# Battery_Tree_V2.net
KiCad netlist of a schematic drawn in EasyEDA Pro
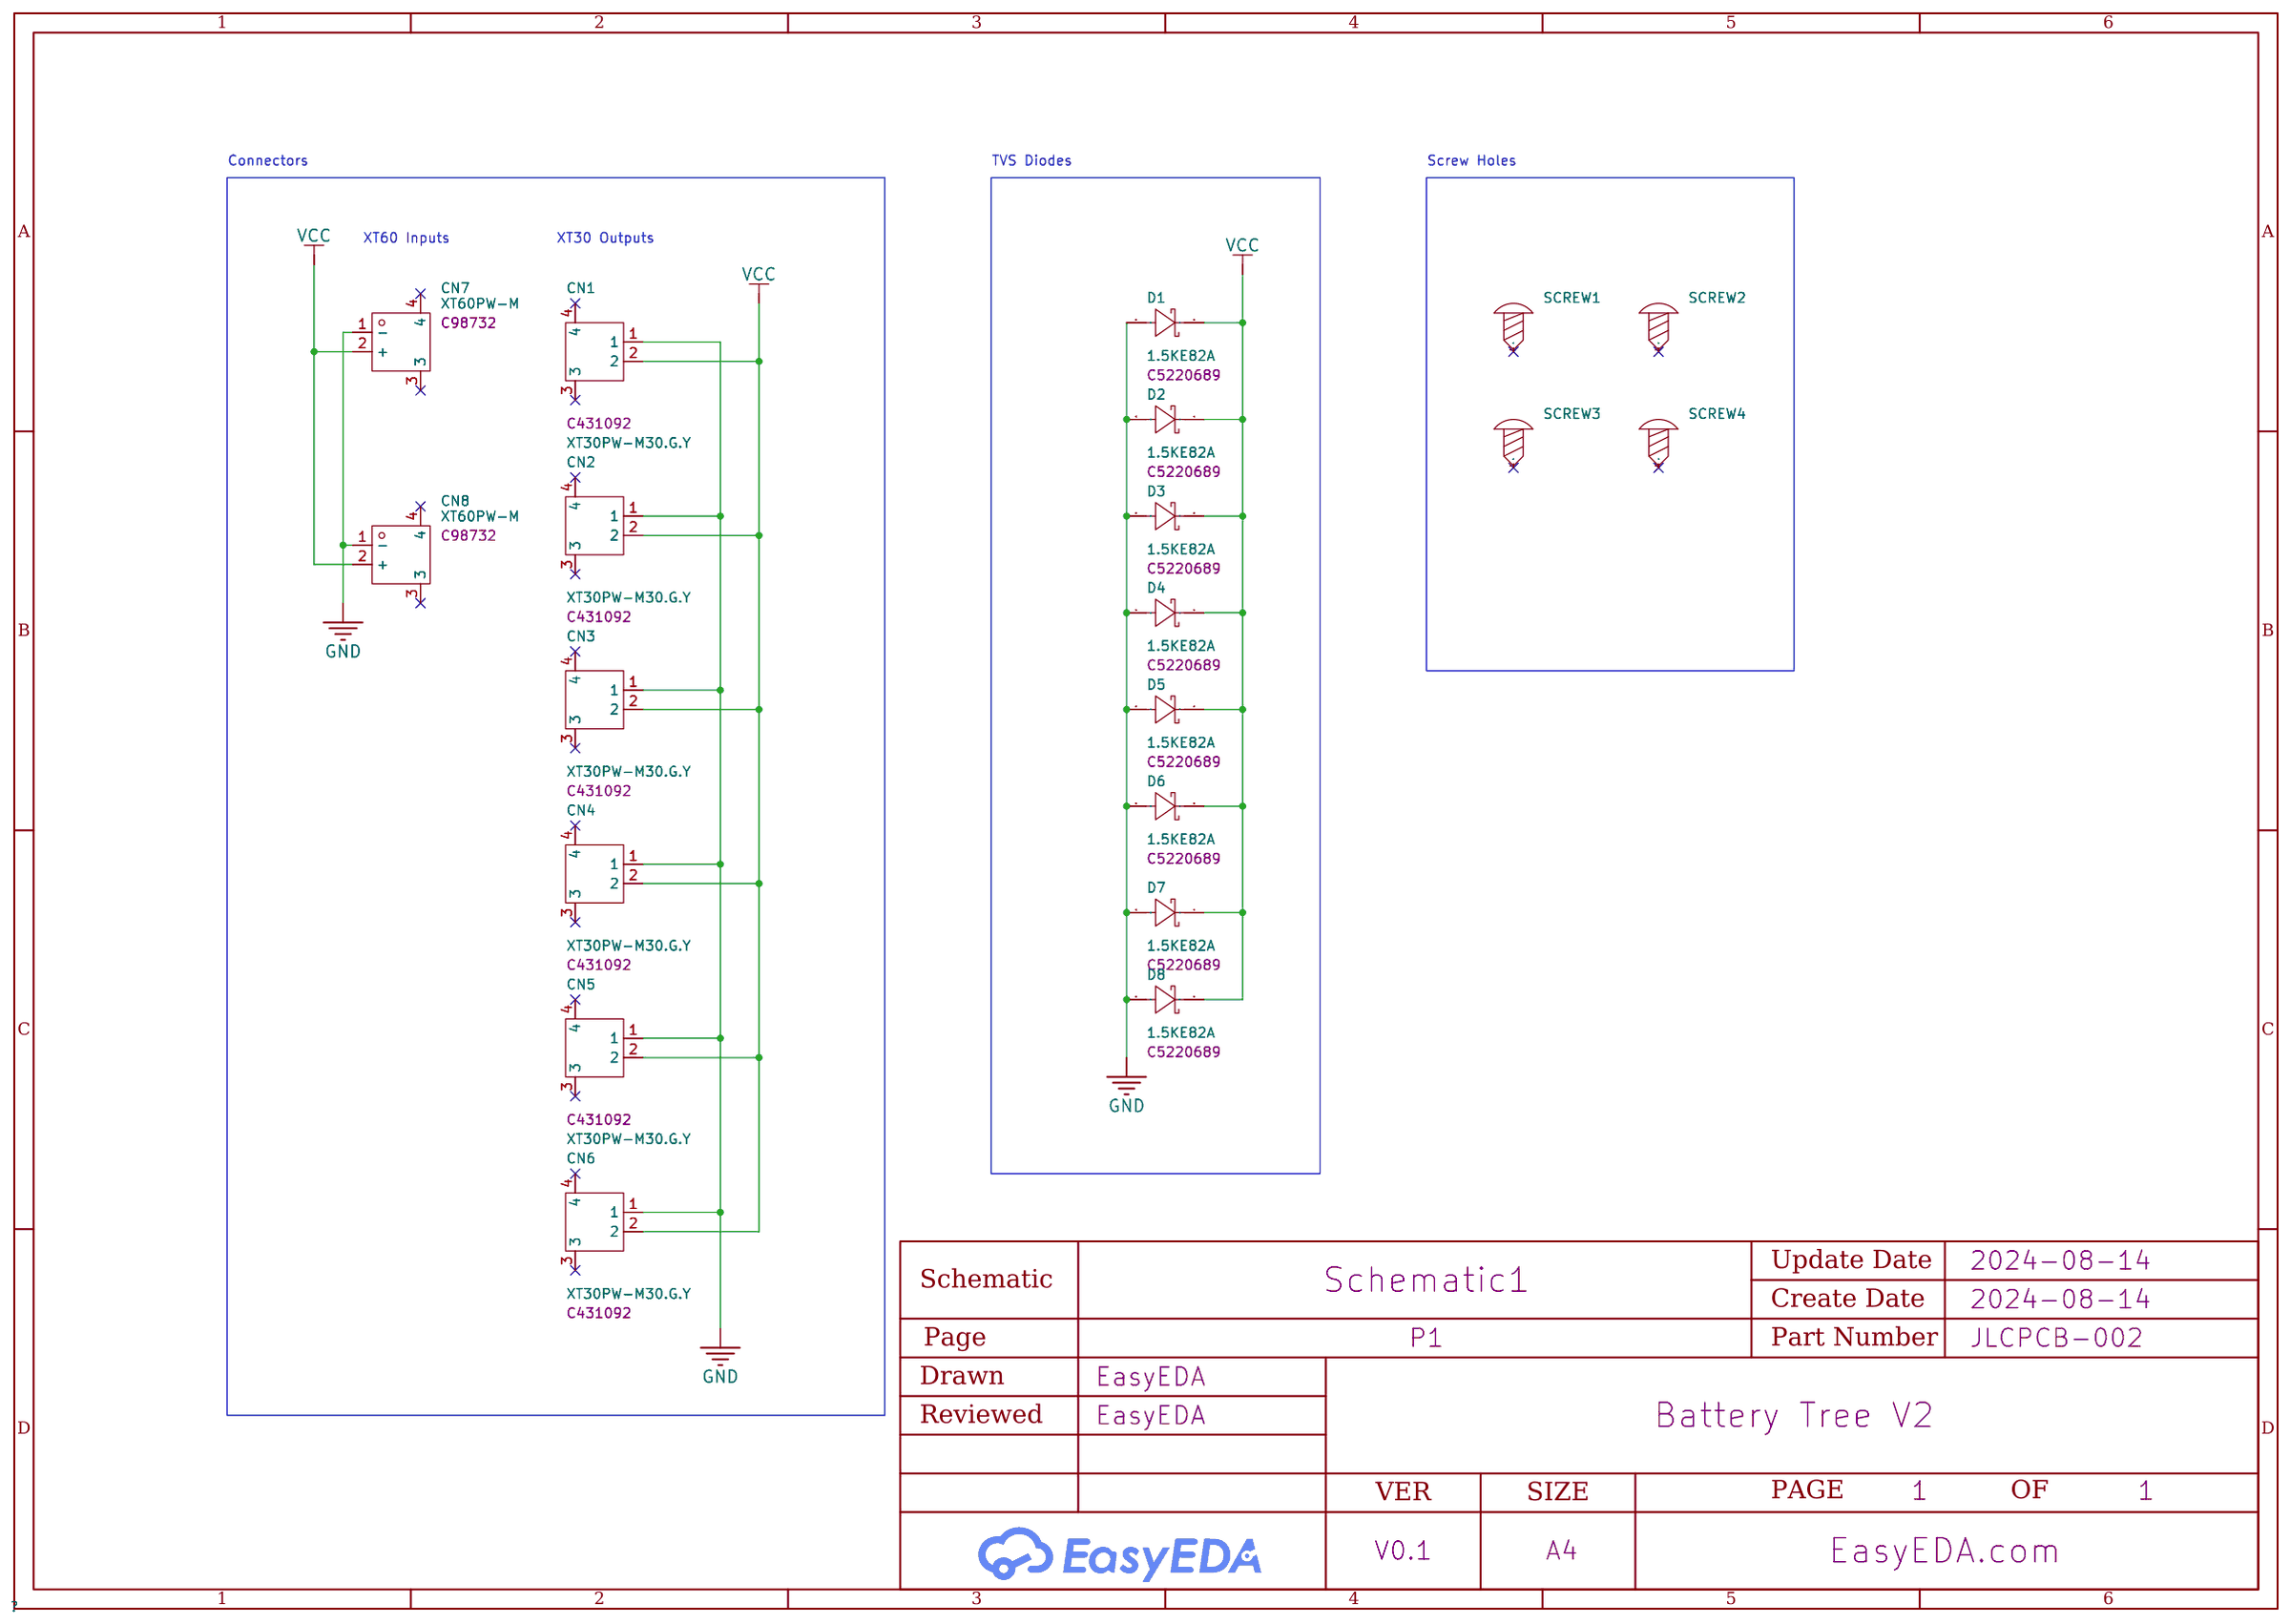
[diagram p0: schematic sheet]

(export (version "E")
  (design (tool "Eeschema 10.0.6"))
  (components
    (comp (ref "CN1")
      (value "XT30PW-M30.G.Y")
      (footprint "easyedapro:CONN-TH_XT30PW-M")
      (fields (field (name "Manufacturer") "AMASS(艾迈斯)") (field (name "Supplier Part") "C431092"))
      (libsource (lib "easyedapro") (part "XT30PW-M"))
    )
    (comp (ref "CN2")
      (value "XT30PW-M30.G.Y")
      (footprint "easyedapro:CONN-TH_XT30PW-M")
      (fields (field (name "Manufacturer") "AMASS(艾迈斯)") (field (name "Supplier Part") "C431092"))
      (libsource (lib "easyedapro") (part "XT30PW-M"))
    )
    (comp (ref "CN3")
      (value "XT30PW-M30.G.Y")
      (footprint "easyedapro:CONN-TH_XT30PW-M")
      (fields (field (name "Manufacturer") "AMASS(艾迈斯)") (field (name "Supplier Part") "C431092"))
      (libsource (lib "easyedapro") (part "XT30PW-M"))
    )
    (comp (ref "CN4")
      (value "XT30PW-M30.G.Y")
      (footprint "easyedapro:CONN-TH_XT30PW-M")
      (fields (field (name "Manufacturer") "AMASS(艾迈斯)") (field (name "Supplier Part") "C431092"))
      (libsource (lib "easyedapro") (part "XT30PW-M"))
    )
    (comp (ref "CN5")
      (value "XT30PW-M30.G.Y")
      (footprint "easyedapro:CONN-TH_XT30PW-M")
      (fields (field (name "Manufacturer") "AMASS(艾迈斯)") (field (name "Supplier Part") "C431092"))
      (libsource (lib "easyedapro") (part "XT30PW-M"))
    )
    (comp (ref "CN6")
      (value "XT30PW-M30.G.Y")
      (footprint "easyedapro:CONN-TH_XT30PW-M")
      (fields (field (name "Manufacturer") "AMASS(艾迈斯)") (field (name "Supplier Part") "C431092"))
      (libsource (lib "easyedapro") (part "XT30PW-M"))
    )
    (comp (ref "CN7")
      (value "XT60PW-M")
      (footprint "easyedapro:CONN-TH_XT60PW-M")
      (fields (field (name "Manufacturer") "AMASS(艾迈斯)") (field (name "Supplier Part") "C98732"))
      (libsource (lib "easyedapro") (part "XT60PW-M"))
    )
    (comp (ref "CN8")
      (value "XT60PW-M")
      (footprint "easyedapro:CONN-TH_XT60PW-M")
      (fields (field (name "Manufacturer") "AMASS(艾迈斯)") (field (name "Supplier Part") "C98732"))
      (libsource (lib "easyedapro") (part "XT60PW-M"))
    )
    (comp (ref "D1")
      (value "1.5KE82A")
      (footprint "easyedapro:DIO-TH_BD5.1-L8.4-P12.40-D1.0-RD")
      (fields
        (field (name "Manufacturer") "Shenzhen Jinkaisheng Elec")
        (field (name "Supplier Part") "C5220689")
      )
      (libsource (lib "easyedapro") (part "1.5KE82AHE3_A/D"))
    )
    (comp (ref "D2")
      (value "1.5KE82A")
      (footprint "easyedapro:DIO-TH_BD5.1-L8.4-P12.40-D1.0-RD")
      (fields
        (field (name "Manufacturer") "Shenzhen Jinkaisheng Elec")
        (field (name "Supplier Part") "C5220689")
      )
      (libsource (lib "easyedapro") (part "1.5KE82AHE3_A/D"))
    )
    (comp (ref "D3")
      (value "1.5KE82A")
      (footprint "easyedapro:DIO-TH_BD5.1-L8.4-P12.40-D1.0-RD")
      (fields
        (field (name "Manufacturer") "Shenzhen Jinkaisheng Elec")
        (field (name "Supplier Part") "C5220689")
      )
      (libsource (lib "easyedapro") (part "1.5KE82AHE3_A/D"))
    )
    (comp (ref "D4")
      (value "1.5KE82A")
      (footprint "easyedapro:DIO-TH_BD5.1-L8.4-P12.40-D1.0-RD")
      (fields
        (field (name "Manufacturer") "Shenzhen Jinkaisheng Elec")
        (field (name "Supplier Part") "C5220689")
      )
      (libsource (lib "easyedapro") (part "1.5KE82AHE3_A/D"))
    )
    (comp (ref "D5")
      (value "1.5KE82A")
      (footprint "easyedapro:DIO-TH_BD5.1-L8.4-P12.40-D1.0-RD")
      (fields
        (field (name "Manufacturer") "Shenzhen Jinkaisheng Elec")
        (field (name "Supplier Part") "C5220689")
      )
      (libsource (lib "easyedapro") (part "1.5KE82AHE3_A/D"))
    )
    (comp (ref "D6")
      (value "1.5KE82A")
      (footprint "easyedapro:DIO-TH_BD5.1-L8.4-P12.40-D1.0-RD")
      (fields
        (field (name "Manufacturer") "Shenzhen Jinkaisheng Elec")
        (field (name "Supplier Part") "C5220689")
      )
      (libsource (lib "easyedapro") (part "1.5KE82AHE3_A/D"))
    )
    (comp (ref "D7")
      (value "1.5KE82A")
      (footprint "easyedapro:DIO-TH_BD5.1-L8.4-P12.40-D1.0-RD")
      (fields
        (field (name "Manufacturer") "Shenzhen Jinkaisheng Elec")
        (field (name "Supplier Part") "C5220689")
      )
      (libsource (lib "easyedapro") (part "1.5KE82AHE3_A/D"))
    )
    (comp (ref "D8")
      (value "1.5KE82A")
      (footprint "easyedapro:DIO-TH_BD5.1-L8.4-P12.40-D1.0-RD")
      (fields
        (field (name "Manufacturer") "Shenzhen Jinkaisheng Elec")
        (field (name "Supplier Part") "C5220689")
      )
      (libsource (lib "easyedapro") (part "1.5KE82AHE3_A/D"))
    )
    (comp (ref "SCREW1")
      (value "~")
      (footprint "easyedapro:Screw-Hole-M3")
      (libsource (lib "easyedapro") (part "Screw-Hole"))
    )
    (comp (ref "SCREW2")
      (value "~")
      (footprint "easyedapro:Screw-Hole-M3")
      (libsource (lib "easyedapro") (part "Screw-Hole"))
    )
    (comp (ref "SCREW3")
      (value "~")
      (footprint "easyedapro:Screw-Hole-M3")
      (libsource (lib "easyedapro") (part "Screw-Hole"))
    )
    (comp (ref "SCREW4")
      (value "~")
      (footprint "easyedapro:Screw-Hole-M3")
      (libsource (lib "easyedapro") (part "Screw-Hole"))
    )
  )
  (nets
    (net (code "1") (name "GND") (class "Default")
      (node (ref "CN1") (pin "1") (pinfunction "1_1") (pintype "unspecified"))
      (node (ref "CN2") (pin "1") (pinfunction "1_1") (pintype "unspecified"))
      (node (ref "CN3") (pin "1") (pinfunction "1_1") (pintype "unspecified"))
      (node (ref "CN4") (pin "1") (pinfunction "1_1") (pintype "unspecified"))
      (node (ref "CN5") (pin "1") (pinfunction "1_1") (pintype "unspecified"))
      (node (ref "CN6") (pin "1") (pinfunction "1_1") (pintype "unspecified"))
      (node (ref "CN7") (pin "1") (pinfunction "-_1") (pintype "unspecified"))
      (node (ref "CN8") (pin "1") (pinfunction "-_1") (pintype "unspecified"))
      (node (ref "D1") (pin "2") (pinfunction "K_2") (pintype "unspecified"))
      (node (ref "D2") (pin "2") (pinfunction "K_2") (pintype "unspecified"))
      (node (ref "D3") (pin "2") (pinfunction "K_2") (pintype "unspecified"))
      (node (ref "D4") (pin "2") (pinfunction "K_2") (pintype "unspecified"))
      (node (ref "D5") (pin "2") (pinfunction "K_2") (pintype "unspecified"))
      (node (ref "D6") (pin "2") (pinfunction "K_2") (pintype "unspecified"))
      (node (ref "D7") (pin "2") (pinfunction "K_2") (pintype "unspecified"))
      (node (ref "D8") (pin "2") (pinfunction "K_2") (pintype "unspecified"))
    )
    (net (code "2") (name "VCC") (class "Default")
      (node (ref "CN1") (pin "2") (pinfunction "2_2") (pintype "unspecified"))
      (node (ref "CN2") (pin "2") (pinfunction "2_2") (pintype "unspecified"))
      (node (ref "CN3") (pin "2") (pinfunction "2_2") (pintype "unspecified"))
      (node (ref "CN4") (pin "2") (pinfunction "2_2") (pintype "unspecified"))
      (node (ref "CN5") (pin "2") (pinfunction "2_2") (pintype "unspecified"))
      (node (ref "CN6") (pin "2") (pinfunction "2_2") (pintype "unspecified"))
      (node (ref "CN7") (pin "2") (pinfunction "+_2") (pintype "unspecified"))
      (node (ref "CN8") (pin "2") (pinfunction "+_2") (pintype "unspecified"))
      (node (ref "D1") (pin "1") (pinfunction "A_1") (pintype "unspecified"))
      (node (ref "D2") (pin "1") (pinfunction "A_1") (pintype "unspecified"))
      (node (ref "D3") (pin "1") (pinfunction "A_1") (pintype "unspecified"))
      (node (ref "D4") (pin "1") (pinfunction "A_1") (pintype "unspecified"))
      (node (ref "D5") (pin "1") (pinfunction "A_1") (pintype "unspecified"))
      (node (ref "D6") (pin "1") (pinfunction "A_1") (pintype "unspecified"))
      (node (ref "D7") (pin "1") (pinfunction "A_1") (pintype "unspecified"))
      (node (ref "D8") (pin "1") (pinfunction "A_1") (pintype "unspecified"))
    )
    (net (code "3") (name "unconnected-(CN1-Pad3)") (class "Default")
      (node (ref "CN1") (pin "3") (pinfunction "3_3") (pintype "unspecified+no_connect"))
    )
    (net (code "4") (name "unconnected-(CN1-Pad4)") (class "Default")
      (node (ref "CN1") (pin "4") (pinfunction "4_4") (pintype "unspecified+no_connect"))
    )
    (net (code "5") (name "unconnected-(CN2-Pad3)") (class "Default")
      (node (ref "CN2") (pin "3") (pinfunction "3_3") (pintype "unspecified+no_connect"))
    )
    (net (code "6") (name "unconnected-(CN2-Pad4)") (class "Default")
      (node (ref "CN2") (pin "4") (pinfunction "4_4") (pintype "unspecified+no_connect"))
    )
    (net (code "7") (name "unconnected-(CN3-Pad3)") (class "Default")
      (node (ref "CN3") (pin "3") (pinfunction "3_3") (pintype "unspecified+no_connect"))
    )
    (net (code "8") (name "unconnected-(CN3-Pad4)") (class "Default")
      (node (ref "CN3") (pin "4") (pinfunction "4_4") (pintype "unspecified+no_connect"))
    )
    (net (code "9") (name "unconnected-(CN4-Pad3)") (class "Default")
      (node (ref "CN4") (pin "3") (pinfunction "3_3") (pintype "unspecified+no_connect"))
    )
    (net (code "10") (name "unconnected-(CN4-Pad4)") (class "Default")
      (node (ref "CN4") (pin "4") (pinfunction "4_4") (pintype "unspecified+no_connect"))
    )
    (net (code "11") (name "unconnected-(CN5-Pad3)") (class "Default")
      (node (ref "CN5") (pin "3") (pinfunction "3_3") (pintype "unspecified+no_connect"))
    )
    (net (code "12") (name "unconnected-(CN5-Pad4)") (class "Default")
      (node (ref "CN5") (pin "4") (pinfunction "4_4") (pintype "unspecified+no_connect"))
    )
    (net (code "13") (name "unconnected-(CN6-Pad3)") (class "Default")
      (node (ref "CN6") (pin "3") (pinfunction "3_3") (pintype "unspecified+no_connect"))
    )
    (net (code "14") (name "unconnected-(CN6-Pad4)") (class "Default")
      (node (ref "CN6") (pin "4") (pinfunction "4_4") (pintype "unspecified+no_connect"))
    )
    (net (code "15") (name "unconnected-(CN7-Pad3)") (class "Default")
      (node (ref "CN7") (pin "3") (pinfunction "3_3") (pintype "unspecified+no_connect"))
    )
    (net (code "16") (name "unconnected-(CN7-Pad4)") (class "Default")
      (node (ref "CN7") (pin "4") (pinfunction "4_4") (pintype "unspecified+no_connect"))
    )
    (net (code "17") (name "unconnected-(CN8-Pad3)") (class "Default")
      (node (ref "CN8") (pin "3") (pinfunction "3_3") (pintype "unspecified+no_connect"))
    )
    (net (code "18") (name "unconnected-(CN8-Pad4)") (class "Default")
      (node (ref "CN8") (pin "4") (pinfunction "4_4") (pintype "unspecified+no_connect"))
    )
    (net (code "19") (name "unconnected-(SCREW1-Pad1)") (class "Default")
      (node (ref "SCREW1") (pin "1") (pinfunction "1_1") (pintype "input+no_connect"))
    )
    (net (code "20") (name "unconnected-(SCREW2-Pad1)") (class "Default")
      (node (ref "SCREW2") (pin "1") (pinfunction "1_1") (pintype "input+no_connect"))
    )
    (net (code "21") (name "unconnected-(SCREW3-Pad1)") (class "Default")
      (node (ref "SCREW3") (pin "1") (pinfunction "1_1") (pintype "input+no_connect"))
    )
    (net (code "22") (name "unconnected-(SCREW4-Pad1)") (class "Default")
      (node (ref "SCREW4") (pin "1") (pinfunction "1_1") (pintype "input+no_connect"))
    )
  )
)
